# test.net
KiCad netlist of a schematic drawn in EasyEDA
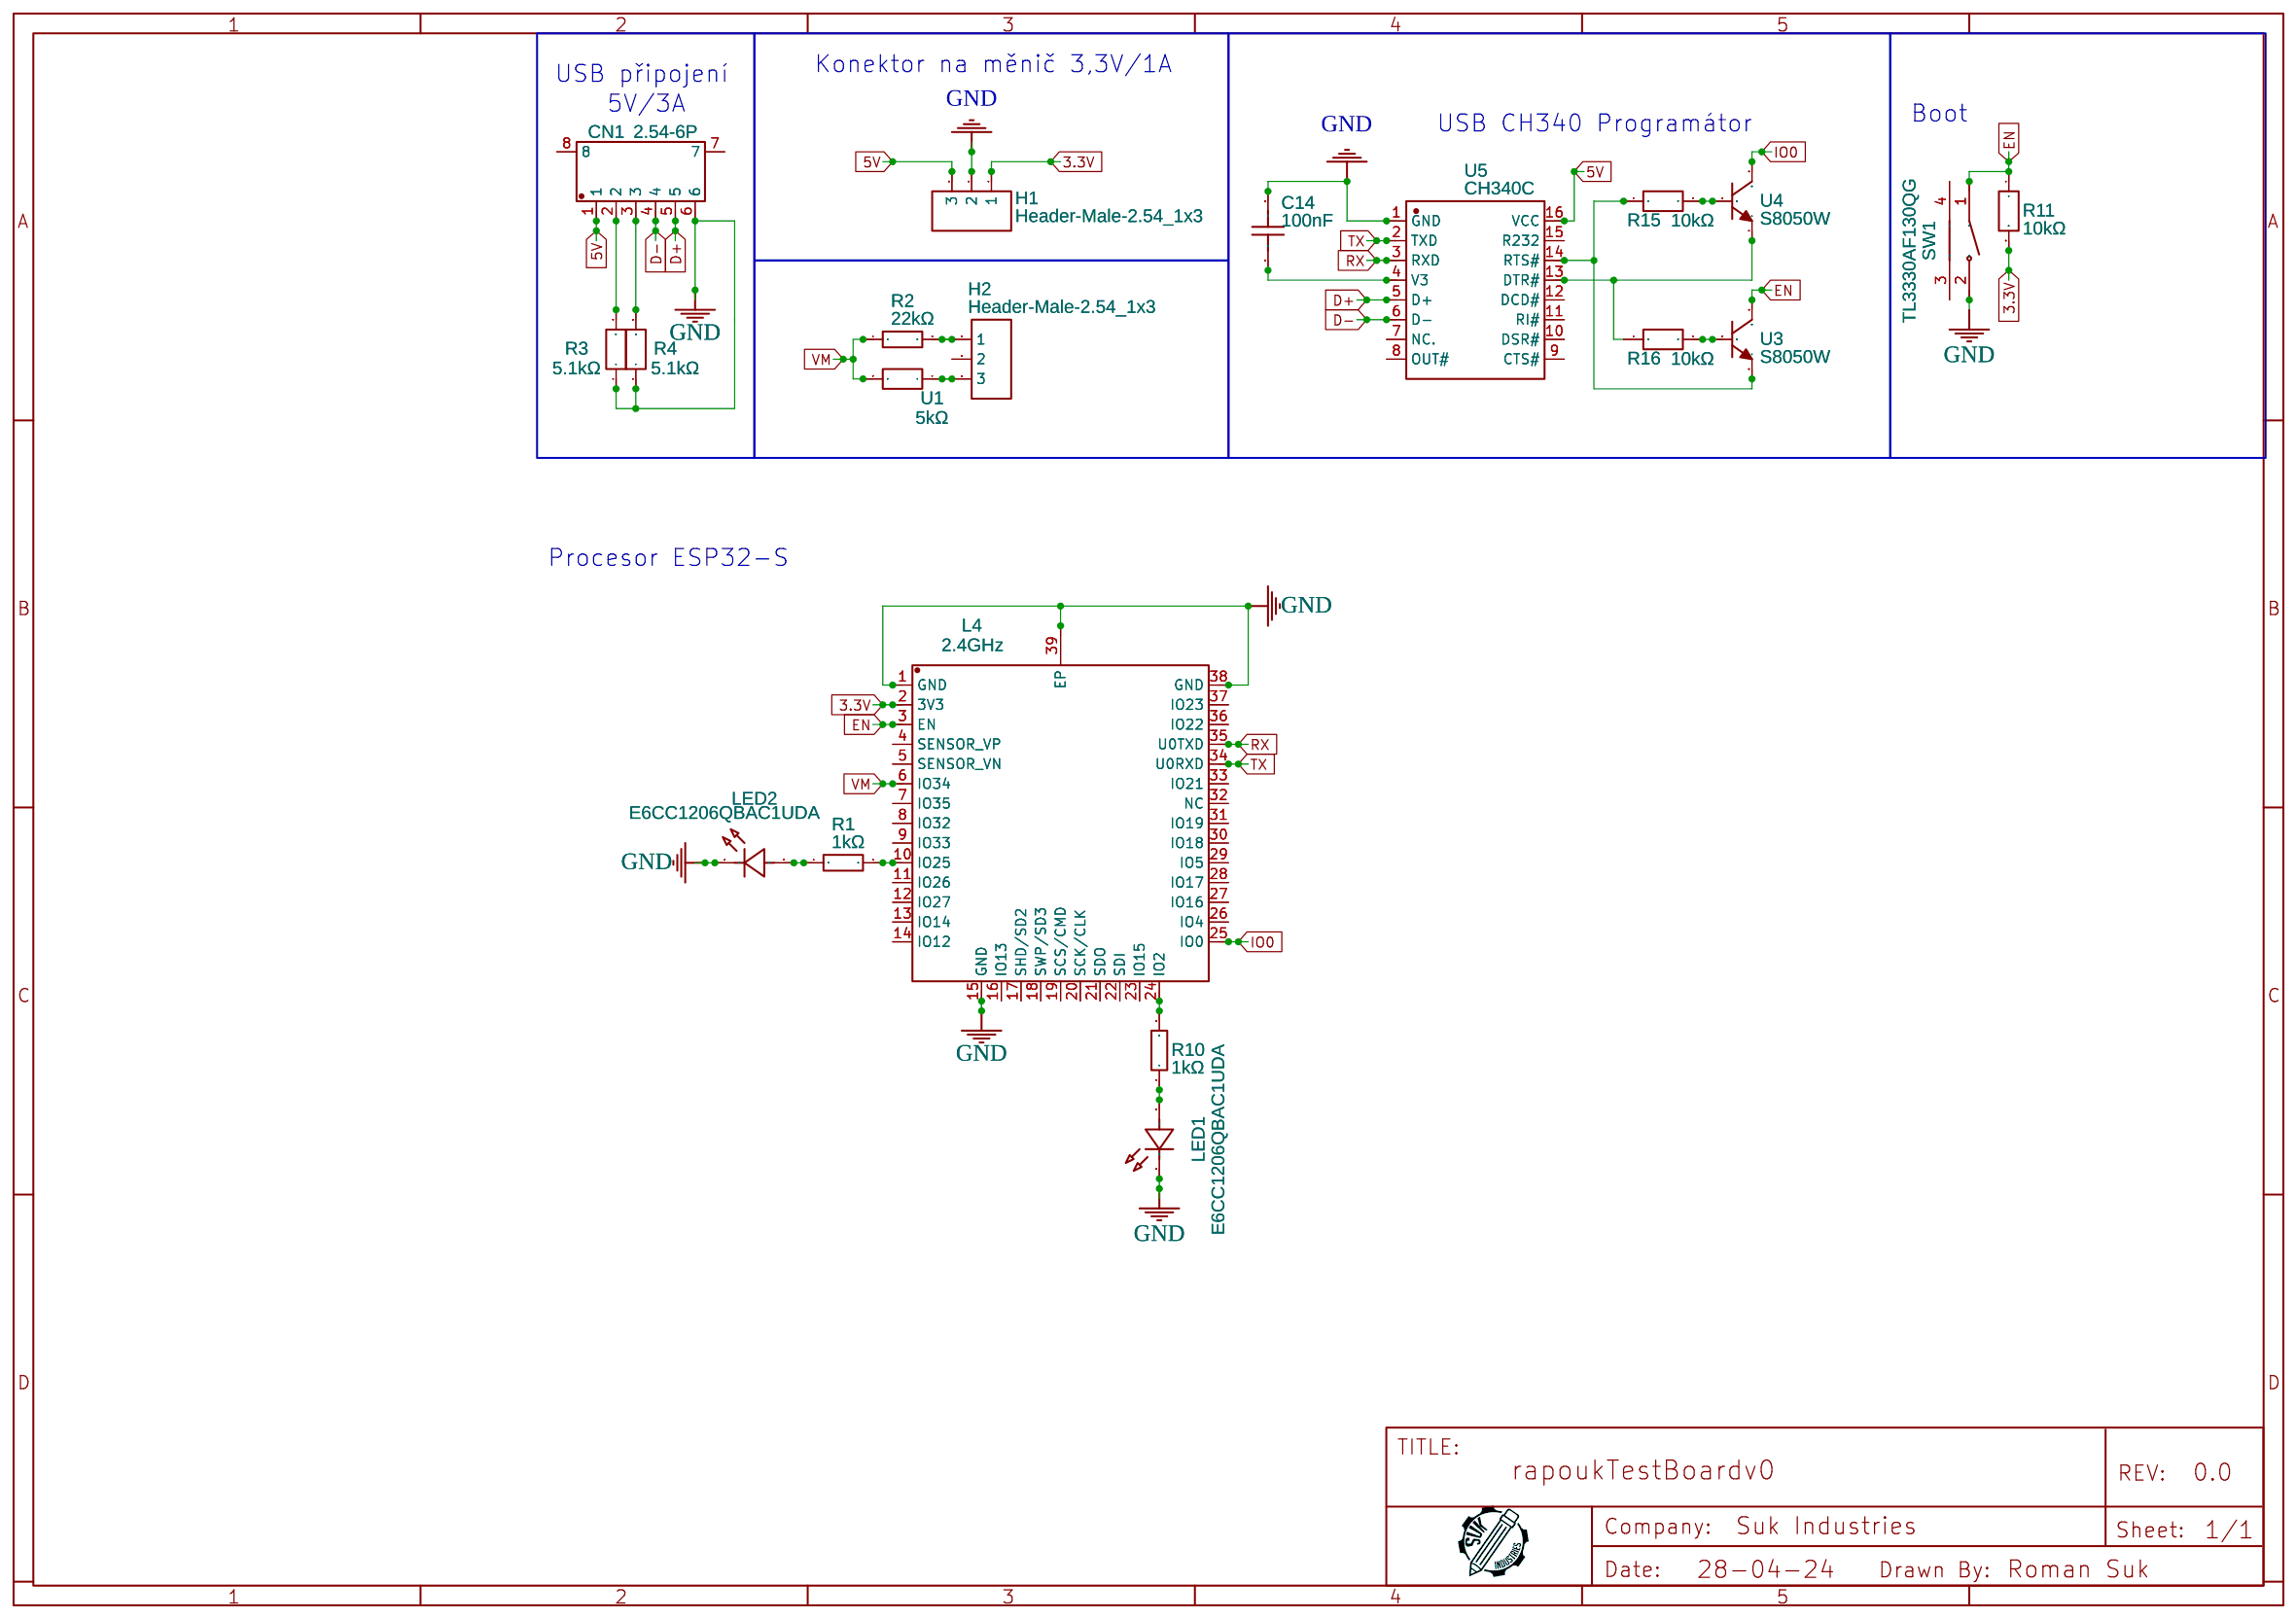
[diagram p0: schematic sheet]

(export (version "E")
  (design (tool "Eeschema 10.0.6"))
  (components
    (comp (ref "C14")
      (value "100nF")
      (fields
        (field (name "Manufacturer Part") "1206Y1000104KXR")
        (field (name "Manufacturer") "Knowles(楼氏)")
      )
      (libsource (lib "") (part "1206Y1000104KXR"))
    )
    (comp (ref "CN1")
      (value "2.54-6P")
      (fields (field (name "Manufacturer Part") "XH-6P卧贴") (field (name "Manufacturer") "BOOMELE(博穆精密)"))
      (libsource (lib "") (part "2.54-6P"))
    )
    (comp (ref "H1")
      (value "Header-Male-2.54_1x3")
      (fields (field (name "Manufacturer Part") "2.54-1*3P针") (field (name "Manufacturer") "BOOMELE(博穆精密)"))
      (libsource (lib "") (part "Header-Male-2.54_1x3_1"))
    )
    (comp (ref "H2")
      (value "Header-Male-2.54_1x3")
      (fields (field (name "Manufacturer Part") "2.54-1*3P针") (field (name "Manufacturer") "BOOMELE(博穆精密)"))
      (libsource (lib "") (part "Header-Male-2.54_1x3"))
    )
    (comp (ref "L4")
      (value "2.4GHz")
      (fields
        (field (name "Manufacturer Part") "ESP32-S(16MB)")
        (field (name "Manufacturer") "Ai-Thinker(安信可)")
      )
      (libsource (lib "") (part "ESP32-S(16MB)"))
    )
    (comp (ref "LED1")
      (value "E6CC1206QBAC1UDA")
      (fields (field (name "Manufacturer") "ekinglux(亿晶源)"))
      (libsource (lib "") (part "E6CC1206QBAC1UDA_1"))
    )
    (comp (ref "LED2")
      (value "E6CC1206QBAC1UDA")
      (fields (field (name "Manufacturer") "ekinglux(亿晶源)"))
      (libsource (lib "") (part "E6CC1206QBAC1UDA"))
    )
    (comp (ref "R1")
      (value "1kΩ")
      (fields (field (name "Manufacturer Part") "CR1206-FX-1001ELF") (field (name "Manufacturer") "BOURNS"))
      (libsource (lib "") (part "CR1206-FX-1001ELF"))
    )
    (comp (ref "R2")
      (value "22kΩ")
      (fields (field (name "Manufacturer Part") "AECR1206F22K0K9") (field (name "Manufacturer") "RESI(开步睿思）"))
      (libsource (lib "") (part "AECR1206F22K0K9"))
    )
    (comp (ref "R3")
      (value "5.1kΩ")
      (fields (field (name "Manufacturer Part") "FRC0603F5101TS") (field (name "Manufacturer") "FOJAN(富捷)"))
      (libsource (lib "") (part "FRC0603F5101TS"))
    )
    (comp (ref "R4")
      (value "5.1kΩ")
      (fields (field (name "Manufacturer Part") "FRC0603F5101TS") (field (name "Manufacturer") "FOJAN(富捷)"))
      (libsource (lib "") (part "FRC0603F5101TS"))
    )
    (comp (ref "R10")
      (value "1kΩ")
      (fields (field (name "Manufacturer Part") "CR1206-FX-1001ELF") (field (name "Manufacturer") "BOURNS"))
      (libsource (lib "") (part "CR1206-FX-1001ELF_1"))
    )
    (comp (ref "R11")
      (value "10kΩ")
      (fields (field (name "Manufacturer Part") "SCR1206F10K") (field (name "Manufacturer") "VO(翔胜)"))
      (libsource (lib "") (part "SCR1206F10K"))
    )
    (comp (ref "R15")
      (value "10kΩ")
      (fields (field (name "Manufacturer Part") "SCR1206F10K") (field (name "Manufacturer") "VO(翔胜)"))
      (libsource (lib "") (part "SCR1206F10K_1"))
    )
    (comp (ref "R16")
      (value "10kΩ")
      (fields (field (name "Manufacturer Part") "SCR1206F10K") (field (name "Manufacturer") "VO(翔胜)"))
      (libsource (lib "") (part "SCR1206F10K_1"))
    )
    (comp (ref "SW1")
      (value "TL3330AF130QG")
      (fields (field (name "Manufacturer") "E-Switch"))
      (libsource (lib "") (part "TL3330AF130QG"))
    )
    (comp (ref "U1")
      (value "5kΩ")
      (fields (field (name "Manufacturer Part") "HVF1206T5001FE") (field (name "Manufacturer") "Ohmite"))
      (libsource (lib "") (part "HVF1206T5001FE"))
    )
    (comp (ref "U3")
      (value "S8050W")
      (fields (field (name "Manufacturer") "Slkor(萨科微)"))
      (libsource (lib "") (part "S8050W"))
    )
    (comp (ref "U4")
      (value "S8050W")
      (fields (field (name "Manufacturer") "Slkor(萨科微)"))
      (libsource (lib "") (part "S8050W"))
    )
    (comp (ref "U5")
      (value "CH340C")
      (fields (field (name "Manufacturer") "WCH(南京沁恒)"))
      (libsource (lib "") (part "CH340C"))
    )
  )
  (nets
    (net (code "1") (name "3.3V") (class "Default")
      (node (ref "H1") (pin "1") (pinfunction "1_1") (pintype "input"))
      (node (ref "L4") (pin "2") (pinfunction "3V3_2") (pintype "unspecified"))
      (node (ref "R11") (pin "2") (pinfunction "2_2") (pintype "unspecified"))
    )
    (net (code "2") (name "5V") (class "Default")
      (node (ref "CN1") (pin "1") (pinfunction "1_1") (pintype "unspecified"))
      (node (ref "H1") (pin "3") (pinfunction "3_3") (pintype "input"))
      (node (ref "U5") (pin "16") (pinfunction "VCC_16") (pintype "unspecified"))
    )
    (net (code "3") (name "D+") (class "Default")
      (node (ref "CN1") (pin "5") (pinfunction "5_5") (pintype "unspecified"))
      (node (ref "U5") (pin "5") (pinfunction "D+_5") (pintype "unspecified"))
    )
    (net (code "4") (name "D-") (class "Default")
      (node (ref "CN1") (pin "4") (pinfunction "4_4") (pintype "unspecified"))
      (node (ref "U5") (pin "6") (pinfunction "D-_6") (pintype "unspecified"))
    )
    (net (code "5") (name "EN") (class "Default")
      (node (ref "L4") (pin "3") (pinfunction "EN_3") (pintype "unspecified"))
      (node (ref "R11") (pin "1") (pinfunction "1_1") (pintype "unspecified"))
      (node (ref "SW1") (pin "1") (pinfunction "1_1") (pintype "unspecified"))
      (node (ref "U3") (pin "3") (pinfunction "C_3") (pintype "unspecified"))
    )
    (net (code "6") (name "GND") (class "Default")
      (node (ref "C14") (pin "2") (pinfunction "2_2") (pintype "unspecified"))
      (node (ref "CN1") (pin "6") (pinfunction "6_6") (pintype "unspecified"))
      (node (ref "H1") (pin "2") (pinfunction "2_2") (pintype "input"))
      (node (ref "L4") (pin "1") (pinfunction "GND_1") (pintype "unspecified"))
      (node (ref "L4") (pin "15") (pinfunction "GND_15") (pintype "unspecified"))
      (node (ref "L4") (pin "38") (pinfunction "GND_38") (pintype "unspecified"))
      (node (ref "L4") (pin "39") (pinfunction "EP_39") (pintype "unspecified"))
      (node (ref "LED1") (pin "1") (pinfunction "K_1") (pintype "unspecified"))
      (node (ref "LED2") (pin "1") (pinfunction "K_1") (pintype "unspecified"))
      (node (ref "R3") (pin "1") (pinfunction "1_1") (pintype "unspecified"))
      (node (ref "R4") (pin "1") (pinfunction "1_1") (pintype "unspecified"))
      (node (ref "SW1") (pin "2") (pinfunction "2_2") (pintype "unspecified"))
      (node (ref "U5") (pin "1") (pinfunction "GND_1") (pintype "unspecified"))
    )
    (net (code "7") (name "IO0") (class "Default")
      (node (ref "L4") (pin "25") (pinfunction "IO0_25") (pintype "unspecified"))
      (node (ref "U4") (pin "3") (pinfunction "C_3") (pintype "unspecified"))
    )
    (net (code "8") (name "Net-(CN1-Pad2)") (class "Default")
      (node (ref "CN1") (pin "2") (pinfunction "2_2") (pintype "unspecified"))
      (node (ref "R3") (pin "2") (pinfunction "2_2") (pintype "unspecified"))
    )
    (net (code "9") (name "Net-(CN1-Pad3)") (class "Default")
      (node (ref "CN1") (pin "3") (pinfunction "3_3") (pintype "unspecified"))
      (node (ref "R4") (pin "2") (pinfunction "2_2") (pintype "unspecified"))
    )
    (net (code "10") (name "Net-(H2-Pad1)") (class "Default")
      (node (ref "H2") (pin "1") (pinfunction "1_1") (pintype "input"))
      (node (ref "R2") (pin "2") (pinfunction "2_2") (pintype "unspecified"))
    )
    (net (code "11") (name "Net-(H2-Pad3)") (class "Default")
      (node (ref "H2") (pin "3") (pinfunction "3_3") (pintype "input"))
      (node (ref "U1") (pin "1") (pinfunction "1_1") (pintype "unspecified"))
    )
    (net (code "12") (name "Net-(L4-IO2)") (class "Default")
      (node (ref "L4") (pin "24") (pinfunction "IO2_24") (pintype "unspecified"))
      (node (ref "R10") (pin "2") (pinfunction "2_2") (pintype "unspecified"))
    )
    (net (code "13") (name "Net-(L4-IO25)") (class "Default")
      (node (ref "L4") (pin "10") (pinfunction "IO25_10") (pintype "unspecified"))
      (node (ref "R1") (pin "2") (pinfunction "2_2") (pintype "unspecified"))
    )
    (net (code "14") (name "Net-(LED1-A)") (class "Default")
      (node (ref "LED1") (pin "2") (pinfunction "A_2") (pintype "unspecified"))
      (node (ref "R10") (pin "1") (pinfunction "1_1") (pintype "unspecified"))
    )
    (net (code "15") (name "Net-(LED2-A)") (class "Default")
      (node (ref "LED2") (pin "2") (pinfunction "A_2") (pintype "unspecified"))
      (node (ref "R1") (pin "1") (pinfunction "1_1") (pintype "unspecified"))
    )
    (net (code "16") (name "Net-(U3-B)") (class "Default")
      (node (ref "R16") (pin "2") (pinfunction "2_2") (pintype "unspecified"))
      (node (ref "U3") (pin "1") (pinfunction "B_1") (pintype "unspecified"))
    )
    (net (code "17") (name "Net-(U3-E)") (class "Default")
      (node (ref "R15") (pin "1") (pinfunction "1_1") (pintype "unspecified"))
      (node (ref "U3") (pin "2") (pinfunction "E_2") (pintype "unspecified"))
      (node (ref "U5") (pin "14") (pinfunction "RTS#_14") (pintype "unspecified"))
    )
    (net (code "18") (name "Net-(U4-B)") (class "Default")
      (node (ref "R15") (pin "2") (pinfunction "2_2") (pintype "unspecified"))
      (node (ref "U4") (pin "1") (pinfunction "B_1") (pintype "unspecified"))
    )
    (net (code "19") (name "Net-(U4-E)") (class "Default")
      (node (ref "R16") (pin "1") (pinfunction "1_1") (pintype "unspecified"))
      (node (ref "U4") (pin "2") (pinfunction "E_2") (pintype "unspecified"))
      (node (ref "U5") (pin "13") (pinfunction "DTR#_13") (pintype "unspecified"))
    )
    (net (code "20") (name "Net-(U5-V3)") (class "Default")
      (node (ref "C14") (pin "1") (pinfunction "1_1") (pintype "unspecified"))
      (node (ref "U5") (pin "4") (pinfunction "V3_4") (pintype "unspecified"))
    )
    (net (code "21") (name "RX") (class "Default")
      (node (ref "L4") (pin "35") (pinfunction "U0TXD_35") (pintype "unspecified"))
      (node (ref "U5") (pin "3") (pinfunction "RXD_3") (pintype "unspecified"))
    )
    (net (code "22") (name "TX") (class "Default")
      (node (ref "L4") (pin "34") (pinfunction "U0RXD_34") (pintype "unspecified"))
      (node (ref "U5") (pin "2") (pinfunction "TXD_2") (pintype "unspecified"))
    )
    (net (code "23") (name "VM") (class "Default")
      (node (ref "L4") (pin "6") (pinfunction "IO34_6") (pintype "unspecified"))
      (node (ref "R2") (pin "1") (pinfunction "1_1") (pintype "unspecified"))
      (node (ref "U1") (pin "2") (pinfunction "2_2") (pintype "unspecified"))
    )
    (net (code "24") (name "unconnected-(CN1-Pad7)") (class "Default")
      (node (ref "CN1") (pin "7") (pinfunction "7_7") (pintype "unspecified"))
    )
    (net (code "25") (name "unconnected-(CN1-Pad8)") (class "Default")
      (node (ref "CN1") (pin "8") (pinfunction "8_8") (pintype "unspecified"))
    )
    (net (code "26") (name "unconnected-(H2-Pad2)") (class "Default")
      (node (ref "H2") (pin "2") (pinfunction "2_2") (pintype "input"))
    )
    (net (code "27") (name "unconnected-(L4-IO4-Pad26)") (class "Default")
      (node (ref "L4") (pin "26") (pinfunction "IO4_26") (pintype "unspecified"))
    )
    (net (code "28") (name "unconnected-(L4-IO5-Pad29)") (class "Default")
      (node (ref "L4") (pin "29") (pinfunction "IO5_29") (pintype "unspecified"))
    )
    (net (code "29") (name "unconnected-(L4-IO12-Pad14)") (class "Default")
      (node (ref "L4") (pin "14") (pinfunction "IO12_14") (pintype "unspecified"))
    )
    (net (code "30") (name "unconnected-(L4-IO13-Pad16)") (class "Default")
      (node (ref "L4") (pin "16") (pinfunction "IO13_16") (pintype "unspecified"))
    )
    (net (code "31") (name "unconnected-(L4-IO14-Pad13)") (class "Default")
      (node (ref "L4") (pin "13") (pinfunction "IO14_13") (pintype "unspecified"))
    )
    (net (code "32") (name "unconnected-(L4-IO15-Pad23)") (class "Default")
      (node (ref "L4") (pin "23") (pinfunction "IO15_23") (pintype "unspecified"))
    )
    (net (code "33") (name "unconnected-(L4-IO16-Pad27)") (class "Default")
      (node (ref "L4") (pin "27") (pinfunction "IO16_27") (pintype "unspecified"))
    )
    (net (code "34") (name "unconnected-(L4-IO17-Pad28)") (class "Default")
      (node (ref "L4") (pin "28") (pinfunction "IO17_28") (pintype "unspecified"))
    )
    (net (code "35") (name "unconnected-(L4-IO18-Pad30)") (class "Default")
      (node (ref "L4") (pin "30") (pinfunction "IO18_30") (pintype "unspecified"))
    )
    (net (code "36") (name "unconnected-(L4-IO19-Pad31)") (class "Default")
      (node (ref "L4") (pin "31") (pinfunction "IO19_31") (pintype "unspecified"))
    )
    (net (code "37") (name "unconnected-(L4-IO21-Pad33)") (class "Default")
      (node (ref "L4") (pin "33") (pinfunction "IO21_33") (pintype "unspecified"))
    )
    (net (code "38") (name "unconnected-(L4-IO22-Pad36)") (class "Default")
      (node (ref "L4") (pin "36") (pinfunction "IO22_36") (pintype "unspecified"))
    )
    (net (code "39") (name "unconnected-(L4-IO23-Pad37)") (class "Default")
      (node (ref "L4") (pin "37") (pinfunction "IO23_37") (pintype "unspecified"))
    )
    (net (code "40") (name "unconnected-(L4-IO26-Pad11)") (class "Default")
      (node (ref "L4") (pin "11") (pinfunction "IO26_11") (pintype "unspecified"))
    )
    (net (code "41") (name "unconnected-(L4-IO27-Pad12)") (class "Default")
      (node (ref "L4") (pin "12") (pinfunction "IO27_12") (pintype "unspecified"))
    )
    (net (code "42") (name "unconnected-(L4-IO32-Pad8)") (class "Default")
      (node (ref "L4") (pin "8") (pinfunction "IO32_8") (pintype "unspecified"))
    )
    (net (code "43") (name "unconnected-(L4-IO33-Pad9)") (class "Default")
      (node (ref "L4") (pin "9") (pinfunction "IO33_9") (pintype "unspecified"))
    )
    (net (code "44") (name "unconnected-(L4-IO35-Pad7)") (class "Default")
      (node (ref "L4") (pin "7") (pinfunction "IO35_7") (pintype "unspecified"))
    )
    (net (code "45") (name "unconnected-(L4-NC-Pad32)") (class "Default")
      (node (ref "L4") (pin "32") (pinfunction "NC_32") (pintype "unspecified"))
    )
    (net (code "46") (name "unconnected-(L4-SCK{slash}CLK-Pad20)") (class "Default")
      (node (ref "L4") (pin "20") (pinfunction "SCK/CLK_20") (pintype "unspecified"))
    )
    (net (code "47") (name "unconnected-(L4-SCS{slash}CMD-Pad19)") (class "Default")
      (node (ref "L4") (pin "19") (pinfunction "SCS/CMD_19") (pintype "unspecified"))
    )
    (net (code "48") (name "unconnected-(L4-SDI-Pad22)") (class "Default")
      (node (ref "L4") (pin "22") (pinfunction "SDI_22") (pintype "unspecified"))
    )
    (net (code "49") (name "unconnected-(L4-SDO-Pad21)") (class "Default")
      (node (ref "L4") (pin "21") (pinfunction "SDO_21") (pintype "unspecified"))
    )
    (net (code "50") (name "unconnected-(L4-SENSOR_VN-Pad5)") (class "Default")
      (node (ref "L4") (pin "5") (pinfunction "SENSOR_VN_5") (pintype "unspecified"))
    )
    (net (code "51") (name "unconnected-(L4-SENSOR_VP-Pad4)") (class "Default")
      (node (ref "L4") (pin "4") (pinfunction "SENSOR_VP_4") (pintype "unspecified"))
    )
    (net (code "52") (name "unconnected-(L4-SHD{slash}SD2-Pad17)") (class "Default")
      (node (ref "L4") (pin "17") (pinfunction "SHD/SD2_17") (pintype "unspecified"))
    )
    (net (code "53") (name "unconnected-(L4-SWP{slash}SD3-Pad18)") (class "Default")
      (node (ref "L4") (pin "18") (pinfunction "SWP/SD3_18") (pintype "unspecified"))
    )
    (net (code "54") (name "unconnected-(SW1-Pad3)") (class "Default")
      (node (ref "SW1") (pin "3") (pinfunction "3_3") (pintype "unspecified"))
    )
    (net (code "55") (name "unconnected-(SW1-Pad4)") (class "Default")
      (node (ref "SW1") (pin "4") (pinfunction "4_4") (pintype "unspecified"))
    )
    (net (code "56") (name "unconnected-(U5-CTS#-Pad9)") (class "Default")
      (node (ref "U5") (pin "9") (pinfunction "CTS#_9") (pintype "unspecified"))
    )
    (net (code "57") (name "unconnected-(U5-DCD#-Pad12)") (class "Default")
      (node (ref "U5") (pin "12") (pinfunction "DCD#_12") (pintype "unspecified"))
    )
    (net (code "58") (name "unconnected-(U5-DSR#-Pad10)") (class "Default")
      (node (ref "U5") (pin "10") (pinfunction "DSR#_10") (pintype "unspecified"))
    )
    (net (code "59") (name "unconnected-(U5-NC.-Pad7)") (class "Default")
      (node (ref "U5") (pin "7") (pinfunction "NC._7") (pintype "unspecified"))
    )
    (net (code "60") (name "unconnected-(U5-OUT#-Pad8)") (class "Default")
      (node (ref "U5") (pin "8") (pinfunction "OUT#_8") (pintype "unspecified"))
    )
    (net (code "61") (name "unconnected-(U5-R232-Pad15)") (class "Default")
      (node (ref "U5") (pin "15") (pinfunction "R232_15") (pintype "unspecified"))
    )
    (net (code "62") (name "unconnected-(U5-RI#-Pad11)") (class "Default")
      (node (ref "U5") (pin "11") (pinfunction "RI#_11") (pintype "unspecified"))
    )
  )
)
